# v1_2.net
KiCad netlist of a schematic drawn in Altium Designer
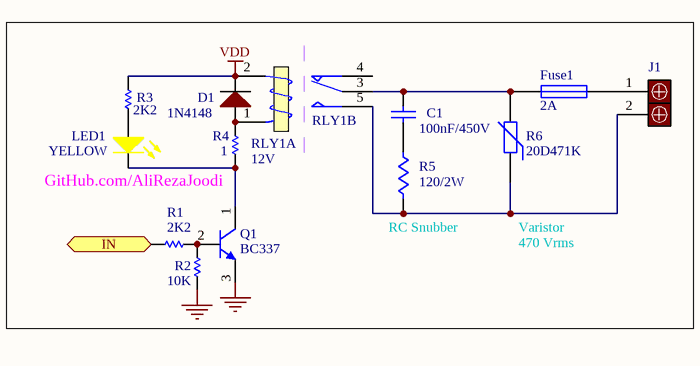
[diagram p0: v1.2.SchDoc]

(export (version "E")
  (design (tool "Eeschema 10.0.6"))
  (components
    (comp (ref "C1")
      (value "100nF/450V")
      (footprint "C_THD_CER_(P2.54-D3.5-T1.5)")
      (description "Capacitor, Ceramic Multilayer")
      (libsource (lib "Passive") (part "Capacitor_Ceramic"))
    )
    (comp (ref "D1")
      (value "1N4148")
      (footprint "D_THD_AXIAL0.3_DO-35")
      (description "Diode,")
      (libsource (lib "Passive") (part "Diode_2Form"))
    )
    (comp (ref "Fuse1")
      (value "2A")
      (footprint "PIN-W2/E2.8")
      (description "Fuse")
      (fields (field (name "MANUFACTURER") "Generic Components") (field (name "PUBLISHER") "Altium Limited"))
      (libsource (lib "Miscellaneous Devices") (part "Fuse 1"))
    )
    (comp (ref "J1")
      (value "2PIN")
      (footprint "Connector_Phoenix_2PIN_MSTB")
      (description "Connector, Header, 2Pin")
      (libsource (lib "Connector") (part "Connector1x2_Power"))
    )
    (comp (ref "LED1")
      (value "YELLOW")
      (footprint "LED_THD_3MM_YELLOW_R")
      (description "LED, Yellow")
      (fields (field (name "MANUFACTURER") "Generic Components") (field (name "PUBLISHER") "Altium Limited"))
      (libsource (lib "Display") (part "LED_YELLOW"))
    )
    (comp (ref "Q1")
      (value "BC337")
      (footprint "TO92C")
      (description "NPN Bipolar Transistor")
      (fields (field (name "MANUFACTURER") "Generic Components") (field (name "PUBLISHER") "Altium Limited"))
      (libsource (lib "Miscellaneous Devices") (part "NPN"))
    )
    (comp (ref "R1")
      (value "2K2")
      (footprint "R_THD_AXIAL0.4(1/4W)")
      (description "Resistor")
      (libsource (lib "Passive") (part "Resistor"))
    )
    (comp (ref "R2")
      (value "10K")
      (footprint "R_THD_AXIAL0.4(1/4W)")
      (description "Resistor")
      (libsource (lib "Passive") (part "Resistor"))
    )
    (comp (ref "R3")
      (value "2K2")
      (footprint "R_THD_AXIAL0.4(1/4W)")
      (description "Resistor")
      (libsource (lib "Passive") (part "Resistor"))
    )
    (comp (ref "R4")
      (value "1")
      (footprint "R_THD_AXIAL0.4(1/4W)")
      (description "Resistor")
      (libsource (lib "Passive") (part "Resistor"))
    )
    (comp (ref "R5")
      (value "120/2W")
      (footprint "R_THD_AXIAL0.9(3W)")
      (description "Resistor")
      (libsource (lib "Passive") (part "Resistor_3Form"))
    )
    (comp (ref "R6")
      (value "20D471K")
      (description "Varistor (Voltage-Sensitive Resistor)")
      (fields (field (name "MANUFACTURER") "Generic Components") (field (name "PUBLISHER") "Altium Limited"))
      (libsource (lib "Miscellaneous Devices") (part "Res Varistor"))
    )
    (comp (ref "RLY1")
      (value "12V")
      (footprint "RELAY_SPDT_5PIN_2216")
      (description "SPDT Relay")
      (libsource (lib "Passive") (part "Relay_SPDT_2Form"))
    )
  )
  (nets
    (net (code "1") (name "/IN") (class "Default")
      (node (ref "R1") (pin "2") (pinfunction "2_2") (pintype "passive"))
    )
    (net (code "2") (name "GND") (class "Default")
      (node (ref "Q1") (pin "3") (pinfunction "E_3") (pintype "passive"))
      (node (ref "R2") (pin "1") (pinfunction "1_1") (pintype "passive"))
    )
    (net (code "3") (name "Net-(C1-Pad1)") (class "Default")
      (node (ref "C1") (pin "1") (pinfunction "1_1") (pintype "passive"))
      (node (ref "R5") (pin "2") (pinfunction "2_2") (pintype "passive"))
    )
    (net (code "4") (name "Net-(D1-A)") (class "Default")
      (node (ref "D1") (pin "1") (pinfunction "A_1") (pintype "passive"))
      (node (ref "R4") (pin "2") (pinfunction "2_2") (pintype "passive"))
      (node (ref "RLY1") (pin "1") (pinfunction "T2_1") (pintype "passive"))
    )
    (net (code "5") (name "Net-(Fuse1-Pad2)") (class "Default")
      (node (ref "Fuse1") (pin "2") (pinfunction "2_2") (pintype "passive"))
      (node (ref "J1") (pin "1") (pinfunction "1_1") (pintype "passive"))
    )
    (net (code "6") (name "Net-(LED1-A)") (class "Default")
      (node (ref "LED1") (pin "1") (pinfunction "A_1") (pintype "passive"))
      (node (ref "R3") (pin "1") (pinfunction "1_1") (pintype "passive"))
    )
    (net (code "7") (name "Net-(LED1-K)") (class "Default")
      (node (ref "LED1") (pin "2") (pinfunction "K_2") (pintype "passive"))
      (node (ref "Q1") (pin "1") (pinfunction "C_1") (pintype "passive"))
      (node (ref "R4") (pin "1") (pinfunction "1_1") (pintype "passive"))
    )
    (net (code "8") (name "Net-(Q1-B)") (class "Default")
      (node (ref "Q1") (pin "2") (pinfunction "B_2") (pintype "passive"))
      (node (ref "R1") (pin "1") (pinfunction "1_1") (pintype "passive"))
      (node (ref "R2") (pin "2") (pinfunction "2_2") (pintype "passive"))
    )
    (net (code "9") (name "Net-(RLY1B-COM)") (class "Default")
      (node (ref "C1") (pin "2") (pinfunction "2_2") (pintype "passive"))
      (node (ref "Fuse1") (pin "1") (pinfunction "1_1") (pintype "passive"))
      (node (ref "R6") (pin "2") (pinfunction "2_2") (pintype "passive"))
      (node (ref "RLY1") (pin "3") (pinfunction "COM_3") (pintype "passive"))
    )
    (net (code "10") (name "Net-(RLY1B-NO)") (class "Default")
      (node (ref "J1") (pin "2") (pinfunction "2_2") (pintype "passive"))
      (node (ref "R5") (pin "1") (pinfunction "1_1") (pintype "passive"))
      (node (ref "R6") (pin "1") (pinfunction "1_1") (pintype "passive"))
      (node (ref "RLY1") (pin "5") (pinfunction "NO_5") (pintype "passive"))
    )
    (net (code "11") (name "VDD") (class "Default")
      (node (ref "D1") (pin "2") (pinfunction "K_2") (pintype "passive"))
      (node (ref "R3") (pin "2") (pinfunction "2_2") (pintype "passive"))
      (node (ref "RLY1") (pin "2") (pinfunction "T1_2") (pintype "passive"))
    )
    (net (code "12") (name "unconnected-(RLY1B-NC-Pad4)") (class "Default")
      (node (ref "RLY1") (pin "4") (pinfunction "NC_4") (pintype "passive"))
    )
  )
)
